# stm32.net
KiCad netlist of a schematic drawn in EasyEDA Pro
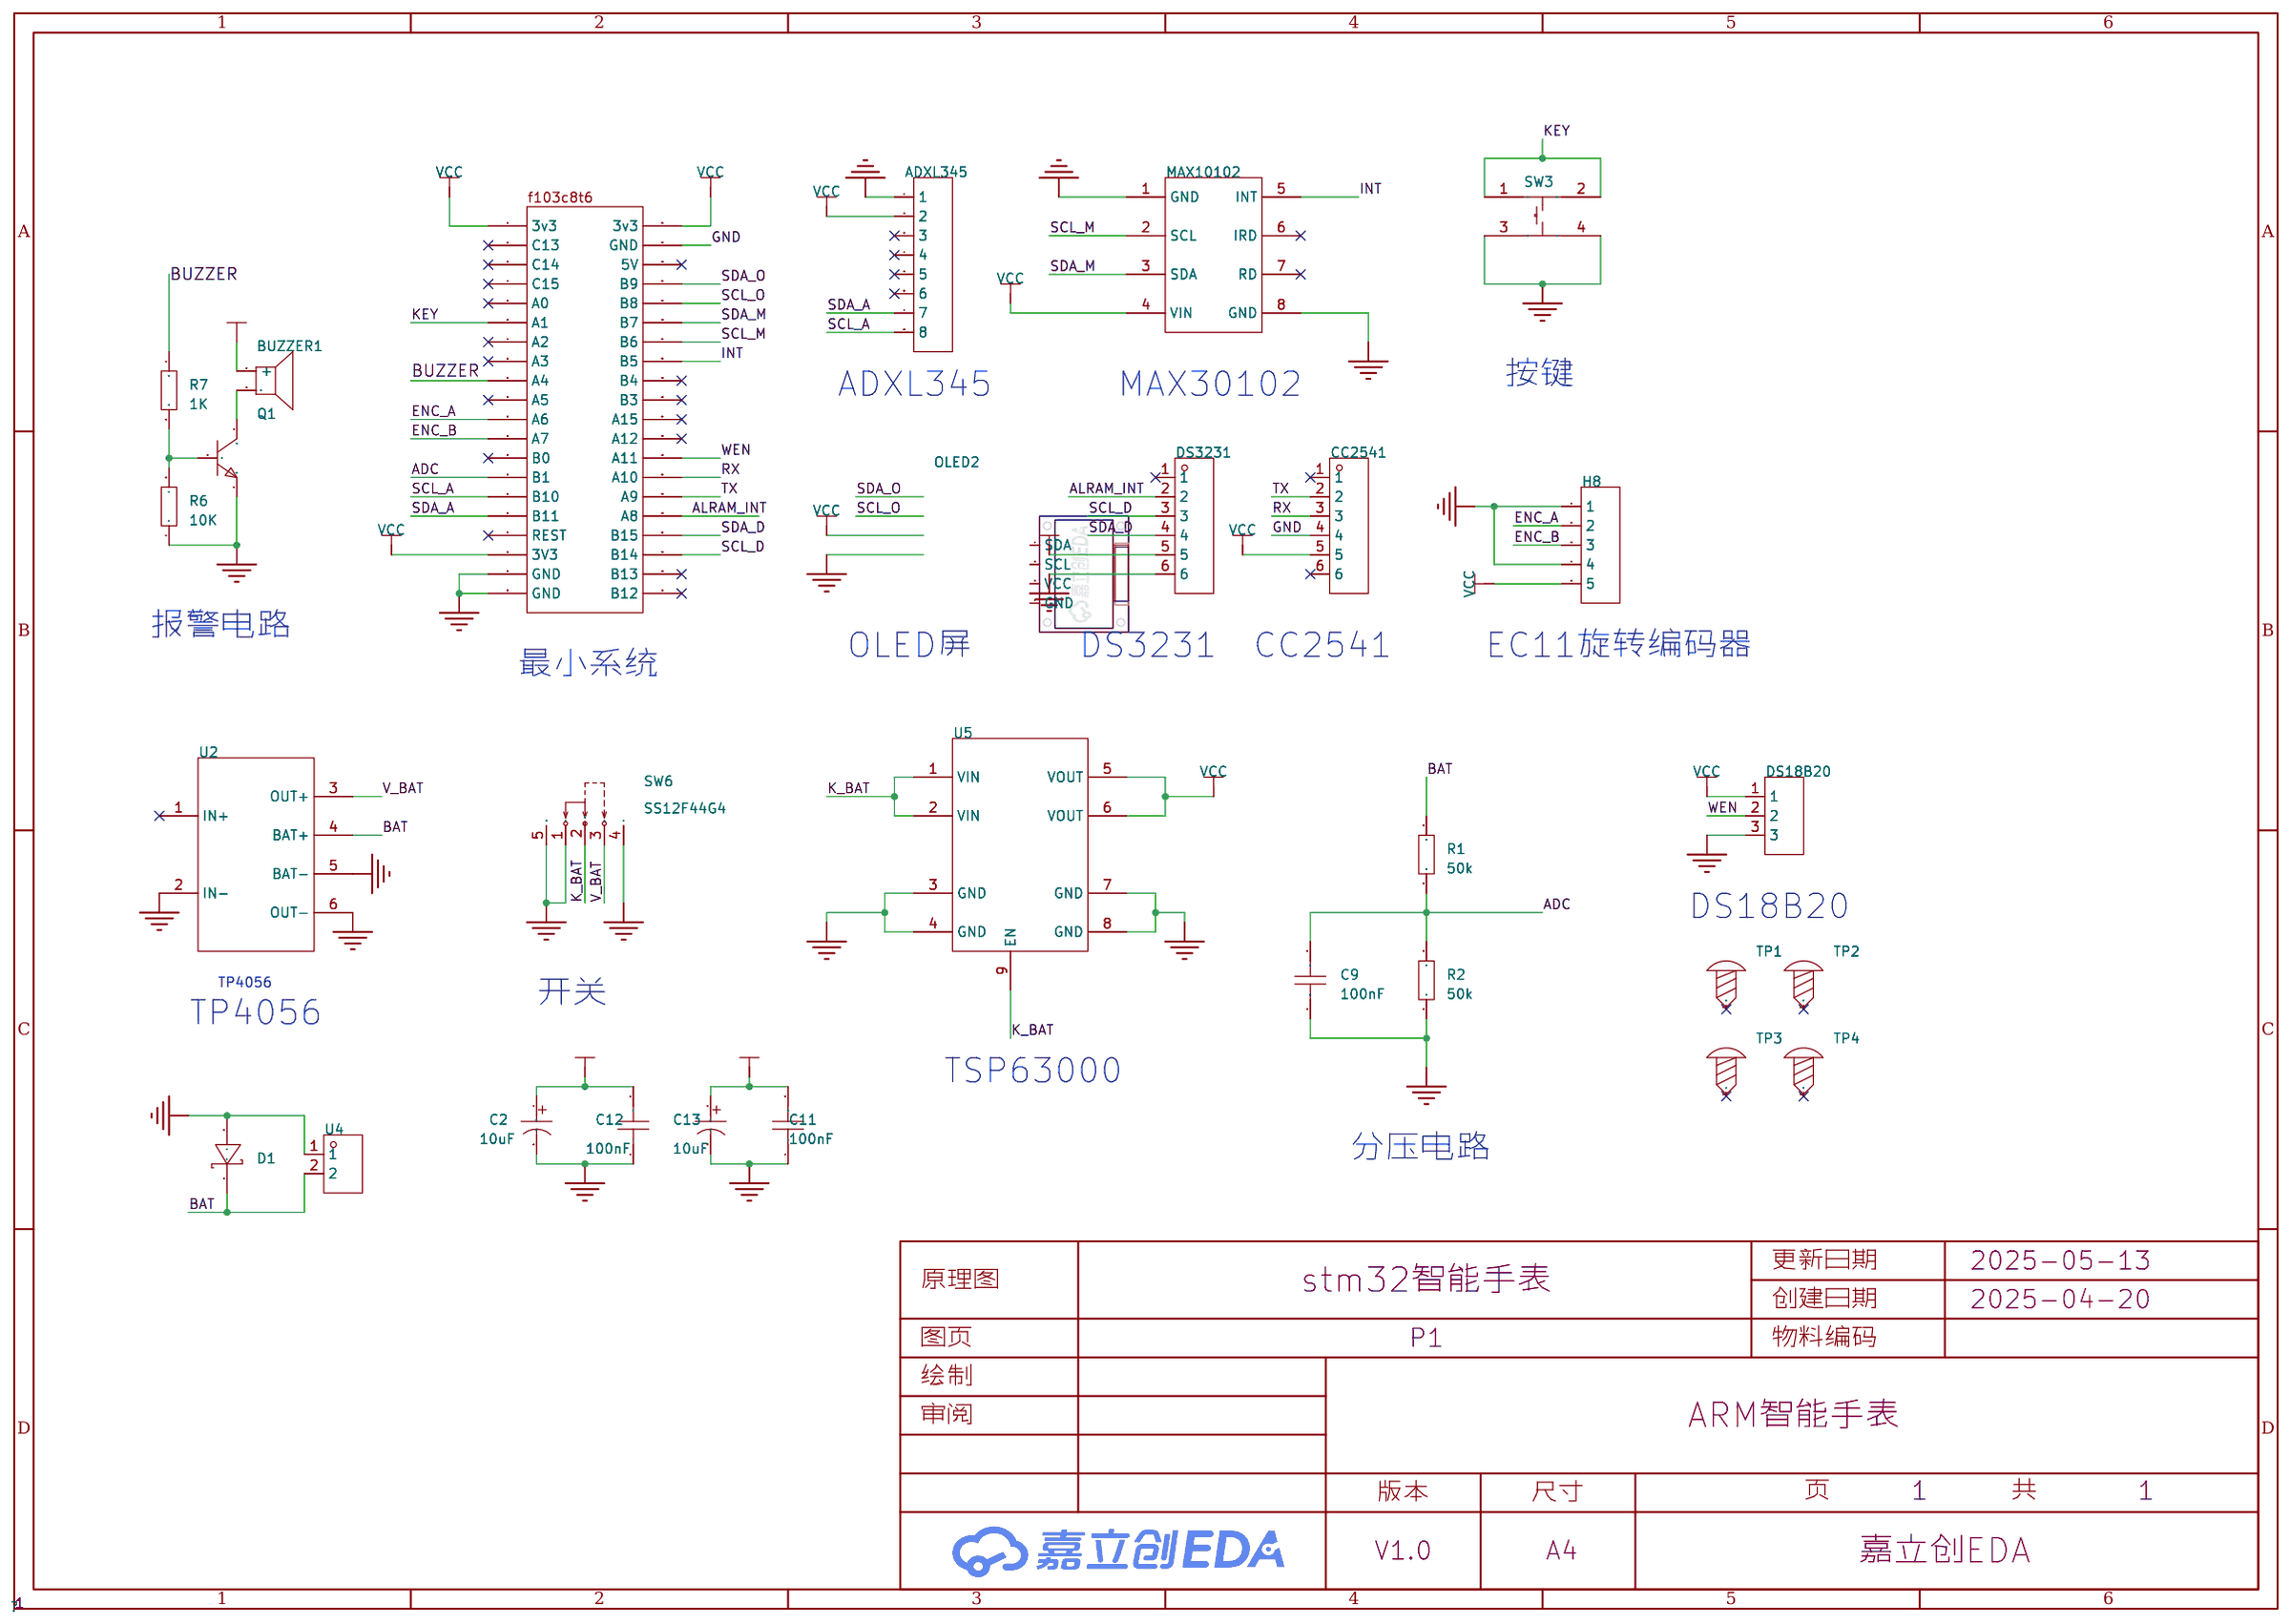
[diagram p0: schematic sheet]

(export (version "E")
  (design (tool "Eeschema 10.0.6"))
  (components
    (comp (ref "ADXL1")
      (value "ADXL345")
      (footprint "easyedapro:HDR-TH_8P-P2.54-V-F-1")
      (libsource (lib "easyedapro") (part "Header-Female-2.54_1x8"))
    )
    (comp (ref "BUZZER1")
      (value "2.3kHz")
      (footprint "easyedapro:BUZ-TH_BD12.0-P7.60-D0.6-FD")
      (description "驱动方式:有源(内含驱动线路);构造类型:电磁式;频率:2.3kHz;声压(SPL):85dB;")
      (fields (field (name "Manufacturer Part") "TMB12A03") (field (name "Manufacturer") "华能"))
      (libsource (lib "easyedapro") (part "TMB12A03"))
    )
    (comp (ref "C2")
      (value "10uF")
      (footprint "easyedapro:CAP-SMD_BD4.0-L4.3-W4.3-FD")
      (description "容值:10uF;精度:±20%;额定电压:35V;纹波电流:15mA@120Hz;等效串联电阻(ESR):-;")
      (fields (field (name "Manufacturer Part") "RVT1V100M0405") (field (name "Manufacturer") "ROQANG(容强)"))
      (libsource (lib "easyedapro") (part "RVT1V100M0405-C72485"))
    )
    (comp (ref "C9")
      (value "100nF")
      (footprint "easyedapro:C0603")
      (libsource (lib "easyedapro") (part "CapAcitance"))
    )
    (comp (ref "C11")
      (value "100nF")
      (footprint "easyedapro:C0603")
      (description "容值:100nF;精度:±10%;额定电压:50V;材质(温度系数):X7R;")
      (fields
        (field (name "Manufacturer Part") "CC0603KRX7R9BB104")
        (field (name "Manufacturer") "YAGEO(国巨)")
      )
      (libsource (lib "easyedapro") (part "CC0603KRX7R9BB104"))
    )
    (comp (ref "C12")
      (value "100nF")
      (footprint "easyedapro:C0603")
      (description "容值:100nF;精度:±10%;额定电压:50V;材质(温度系数):X7R;")
      (fields
        (field (name "Manufacturer Part") "CC0603KRX7R9BB104")
        (field (name "Manufacturer") "YAGEO(国巨)")
      )
      (libsource (lib "easyedapro") (part "CC0603KRX7R9BB104"))
    )
    (comp (ref "C13")
      (value "10uF")
      (footprint "easyedapro:CAP-SMD_BD4.0-L4.3-W4.3-FD")
      (description "容值:10uF;精度:±20%;额定电压:35V;纹波电流:15mA@120Hz;等效串联电阻(ESR):-;")
      (fields (field (name "Manufacturer Part") "RVT1V100M0405") (field (name "Manufacturer") "ROQANG(容强)"))
      (libsource (lib "easyedapro") (part "RVT1V100M0405-C72485"))
    )
    (comp (ref "CC2541")
      (value "~")
      (footprint "easyedapro:HDR-TH_6P-P2.54-V-F")
      (libsource (lib "easyedapro") (part "Header-Female-2.54_1x6"))
    )
    (comp (ref "D1")
      (value "1N5819WS")
      (footprint "easyedapro:SOD-323_L1.8-W1.3-LS2.5-RD")
      (description "正向压降(Vf):600mV@1A;直流反向耐压(Vr):40V;整流电流:1A;")
      (fields (field (name "Manufacturer") "Hottech(合科泰)"))
      (libsource (lib "easyedapro") (part "1N5819WS"))
    )
    (comp (ref "DS1")
      (value "DS3231")
      (footprint "easyedapro:HDR-TH_6P-P2.54-V-F")
      (libsource (lib "easyedapro") (part "Header-Female-2.54_1x6"))
    )
    (comp (ref "H8")
      (value "~")
      (footprint "easyedapro:HDR-TH_5P-P2.54-V-F")
      (libsource (lib "easyedapro") (part "Header-Female-2.54_1x5"))
    )
    (comp (ref "H9")
      (value "DS18B20")
      (footprint "easyedapro:HDR-TH_3P-P2.54-V-F")
      (libsource (lib "easyedapro") (part "PM254V-11-03-H85"))
    )
    (comp (ref "MAX10102")
      (value "~")
      (footprint "easyedapro:MAX30102")
      (libsource (lib "easyedapro") (part "MAX30102"))
    )
    (comp (ref "OLED2")
      (value "~")
      (footprint "easyedapro:0.96OLED_4P")
      (libsource (lib "easyedapro") (part "0.96OLED模块_4P"))
    )
    (comp (ref "Q1")
      (value "~")
      (footprint "easyedapro:S8050_SOT-23")
      (libsource (lib "easyedapro") (part "NPN"))
    )
    (comp (ref "R1") (value "50k") (footprint "easyedapro:R0603") (libsource (lib "easyedapro") (part "电阻")))
    (comp (ref "R2") (value "50k") (footprint "easyedapro:R0603") (libsource (lib "easyedapro") (part "电阻")))
    (comp (ref "R6") (value "10K") (libsource (lib "easyedapro") (part "电阻")))
    (comp (ref "R7") (value "1K") (libsource (lib "easyedapro") (part "电阻")))
    (comp (ref "SCREW1")
      (value "TP1")
      (footprint "easyedapro:M3螺丝")
      (libsource (lib "easyedapro") (part "螺丝孔"))
    )
    (comp (ref "SCREW2")
      (value "TP2")
      (footprint "easyedapro:M3螺丝")
      (libsource (lib "easyedapro") (part "螺丝孔"))
    )
    (comp (ref "SCREW3")
      (value "TP3")
      (footprint "easyedapro:M3螺丝")
      (libsource (lib "easyedapro") (part "螺丝孔"))
    )
    (comp (ref "SCREW4")
      (value "TP4")
      (footprint "easyedapro:M3螺丝")
      (libsource (lib "easyedapro") (part "螺丝孔"))
    )
    (comp (ref "SW3")
      (value "TS-1002-07026")
      (footprint "easyedapro:SW-TH_4P-L6.0-W6.0-P4.50-LS6.5")
      (description "电路结构:单刀单掷;按钮形状:圆形按钮;安装方式:直插;开关长度:6mm;开关宽度:6mm;开关高度:7mm;触点电流:50mA;额定电压(DC):12V;带灯:-;机械寿命:-;")
      (fields (field (name "Manufacturer") "XUNPU(讯普)"))
      (libsource (lib "easyedapro") (part "TS-1002-07026"))
    )
    (comp (ref "SW6")
      (value "SS12F44G4")
      (footprint "easyedapro:SW-TH_SHOU-HAN_SS12F44G4")
      (description "电路结构:单刀双掷;安装方式:直插;开关颜色:-;额定电流(DC):300mA;额定电压(DC):50V;额定电流(AC):-;额定电压(AC):-;机械寿命:5千次;")
      (fields (field (name "Manufacturer") "SHOU HAN(首韩)"))
      (libsource (lib "easyedapro") (part "SS12F44G4"))
    )
    (comp (ref "U1")
      (value "~")
      (footprint "easyedapro:stm32f103c8t6最小系统板")
      (libsource (lib "easyedapro") (part "stm32f103c8t6最小系统板"))
    )
    (comp (ref "U2")
      (value "~")
      (footprint "easyedapro:TP4056")
      (libsource (lib "easyedapro") (part "TP4056模块"))
    )
    (comp (ref "U4")
      (value "XY-XHB2.54-2A21")
      (footprint "easyedapro:HDR-TH_2P-P2.50-H-F-W7.3-N")
      (description "插针结构:1x2P;间距:2.54mm;安装方式:弯插;总PIN数:2P;排数:1;每排PIN数:2;行距:2.54mm;额定电流:2A;工作温度范围:-25°C~+85°C;")
      (fields (field (name "Manufacturer") "XYECONN(辛译)"))
      (libsource (lib "easyedapro") (part "XY-XHB2.54-2A21"))
    )
    (comp (ref "U5")
      (value "~")
      (footprint "easyedapro:TPS63000")
      (libsource (lib "easyedapro") (part "TPS63000"))
    )
  )
  (nets
    (net (code "1") (name "/ADC") (class "Default")
      (node (ref "C9") (pin "2") (pinfunction "2_2") (pintype "input"))
      (node (ref "R1") (pin "1") (pinfunction "1_1") (pintype "input"))
      (node (ref "R2") (pin "2") (pinfunction "2_2") (pintype "input"))
      (node (ref "U1") (pin "14") (pinfunction "B1_14") (pintype "input"))
    )
    (net (code "2") (name "/ALRAM_INT") (class "Default")
      (node (ref "DS1") (pin "2") (pinfunction "2_2") (pintype "unspecified"))
      (node (ref "U1") (pin "36") (pinfunction "A8_36") (pintype "input"))
    )
    (net (code "3") (name "/BAT") (class "Default")
      (node (ref "D1") (pin "1") (pinfunction "K_1") (pintype "unspecified"))
      (node (ref "R1") (pin "2") (pinfunction "2_2") (pintype "input"))
      (node (ref "U2") (pin "4") (pinfunction "BAT+_4") (pintype "input"))
      (node (ref "U4") (pin "2") (pinfunction "2_2") (pintype "unspecified"))
    )
    (net (code "4") (name "/BUZZER") (class "Default")
      (node (ref "R7") (pin "1") (pinfunction "1_1") (pintype "input"))
      (node (ref "U1") (pin "9") (pinfunction "A4_9") (pintype "input"))
    )
    (net (code "5") (name "/ENC_A") (class "Default")
      (node (ref "H8") (pin "2") (pinfunction "2_2") (pintype "input"))
      (node (ref "U1") (pin "11") (pinfunction "A6_11") (pintype "input"))
    )
    (net (code "6") (name "/ENC_B") (class "Default")
      (node (ref "H8") (pin "3") (pinfunction "3_3") (pintype "input"))
      (node (ref "U1") (pin "12") (pinfunction "A7_12") (pintype "input"))
    )
    (net (code "7") (name "/INT") (class "Default")
      (node (ref "MAX10102") (pin "5") (pinfunction "INT_5") (pintype "input"))
      (node (ref "U1") (pin "28") (pinfunction "B5_28") (pintype "input"))
    )
    (net (code "8") (name "/KEY") (class "Default")
      (node (ref "SW3") (pin "1") (pinfunction "1_1") (pintype "unspecified"))
      (node (ref "SW3") (pin "2") (pinfunction "2_2") (pintype "unspecified"))
      (node (ref "U1") (pin "6") (pinfunction "A1_6") (pintype "input"))
    )
    (net (code "9") (name "/RX") (class "Default")
      (node (ref "CC2541") (pin "3") (pinfunction "3_3") (pintype "unspecified"))
      (node (ref "U1") (pin "34") (pinfunction "A10_34") (pintype "input"))
    )
    (net (code "10") (name "/SCL_A") (class "Default")
      (node (ref "ADXL1") (pin "8") (pinfunction "8_8") (pintype "input"))
      (node (ref "U1") (pin "15") (pinfunction "B10_15") (pintype "input"))
    )
    (net (code "11") (name "/SCL_D") (class "Default")
      (node (ref "DS1") (pin "3") (pinfunction "3_3") (pintype "unspecified"))
      (node (ref "U1") (pin "38") (pinfunction "B14_38") (pintype "input"))
    )
    (net (code "12") (name "/SCL_M") (class "Default")
      (node (ref "MAX10102") (pin "2") (pinfunction "SCL_2") (pintype "input"))
      (node (ref "U1") (pin "27") (pinfunction "B6_27") (pintype "input"))
    )
    (net (code "13") (name "/SCL_O") (class "Default")
      (node (ref "U1") (pin "25") (pinfunction "B8_25") (pintype "input"))
    )
    (net (code "14") (name "/SDA_A") (class "Default")
      (node (ref "ADXL1") (pin "7") (pinfunction "7_7") (pintype "input"))
      (node (ref "U1") (pin "16") (pinfunction "B11_16") (pintype "input"))
    )
    (net (code "15") (name "/SDA_D") (class "Default")
      (node (ref "DS1") (pin "4") (pinfunction "4_4") (pintype "unspecified"))
      (node (ref "U1") (pin "37") (pinfunction "B15_37") (pintype "input"))
    )
    (net (code "16") (name "/SDA_M") (class "Default")
      (node (ref "MAX10102") (pin "3") (pinfunction "SDA_3") (pintype "input"))
      (node (ref "U1") (pin "26") (pinfunction "B7_26") (pintype "input"))
    )
    (net (code "17") (name "/SDA_O") (class "Default")
      (node (ref "U1") (pin "24") (pinfunction "B9_24") (pintype "input"))
    )
    (net (code "18") (name "/TX") (class "Default")
      (node (ref "CC2541") (pin "2") (pinfunction "2_2") (pintype "unspecified"))
      (node (ref "U1") (pin "35") (pinfunction "A9_35") (pintype "input"))
    )
    (net (code "19") (name "/V_BAT") (class "Default")
      (node (ref "SW6") (pin "3") (pinfunction "3_3") (pintype "unspecified"))
      (node (ref "U2") (pin "3") (pinfunction "OUT+_3") (pintype "input"))
    )
    (net (code "20") (name "/WEN") (class "Default")
      (node (ref "H9") (pin "2") (pinfunction "2_2") (pintype "unspecified"))
      (node (ref "U1") (pin "33") (pinfunction "A11_33") (pintype "input"))
    )
    (net (code "21") (name "GND") (class "Default")
      (node (ref "ADXL1") (pin "1") (pinfunction "1_1") (pintype "input"))
      (node (ref "C11") (pin "1") (pinfunction "1_1") (pintype "unspecified"))
      (node (ref "C12") (pin "1") (pinfunction "1_1") (pintype "unspecified"))
      (node (ref "C13") (pin "2") (pinfunction "2_2") (pintype "input"))
      (node (ref "C2") (pin "2") (pinfunction "2_2") (pintype "input"))
      (node (ref "C9") (pin "1") (pinfunction "1_1") (pintype "input"))
      (node (ref "CC2541") (pin "4") (pinfunction "4_4") (pintype "unspecified"))
      (node (ref "D1") (pin "2") (pinfunction "A_2") (pintype "unspecified"))
      (node (ref "DS1") (pin "6") (pinfunction "6_6") (pintype "unspecified"))
      (node (ref "H8") (pin "1") (pinfunction "1_1") (pintype "input"))
      (node (ref "H8") (pin "4") (pinfunction "4_4") (pintype "input"))
      (node (ref "H9") (pin "3") (pinfunction "3_3") (pintype "unspecified"))
      (node (ref "MAX10102") (pin "1") (pinfunction "GND_1") (pintype "input"))
      (node (ref "MAX10102") (pin "8") (pinfunction "GND_8") (pintype "input"))
      (node (ref "Q1") (pin "2") (pinfunction "2_2") (pintype "unspecified"))
      (node (ref "R2") (pin "1") (pinfunction "1_1") (pintype "input"))
      (node (ref "R6") (pin "1") (pinfunction "1_1") (pintype "input"))
      (node (ref "SW3") (pin "3") (pinfunction "3_3") (pintype "unspecified"))
      (node (ref "SW3") (pin "4") (pinfunction "4_4") (pintype "unspecified"))
      (node (ref "SW6") (pin "1") (pinfunction "1_1") (pintype "unspecified"))
      (node (ref "SW6") (pin "4") (pinfunction "4_4") (pintype "unspecified"))
      (node (ref "SW6") (pin "5") (pinfunction "5_5") (pintype "unspecified"))
      (node (ref "U1") (pin "19") (pinfunction "GND_19") (pintype "input"))
      (node (ref "U1") (pin "20") (pinfunction "GND_20") (pintype "input"))
      (node (ref "U1") (pin "22") (pinfunction "GND_22") (pintype "input"))
      (node (ref "U2") (pin "2") (pinfunction "IN-_2") (pintype "input"))
      (node (ref "U2") (pin "5") (pinfunction "BAT-_5") (pintype "input"))
      (node (ref "U2") (pin "6") (pinfunction "OUT-_6") (pintype "input"))
      (node (ref "U4") (pin "1") (pinfunction "1_1") (pintype "unspecified"))
      (node (ref "U5") (pin "3") (pinfunction "GND_3") (pintype "input"))
      (node (ref "U5") (pin "4") (pinfunction "GND_4") (pintype "input"))
      (node (ref "U5") (pin "7") (pinfunction "GND_7") (pintype "input"))
      (node (ref "U5") (pin "8") (pinfunction "GND_8") (pintype "input"))
    )
    (net (code "22") (name "K_BAT") (class "Default")
      (node (ref "C12") (pin "2") (pinfunction "2_2") (pintype "unspecified"))
      (node (ref "C2") (pin "1") (pinfunction "1_1") (pintype "input"))
      (node (ref "SW6") (pin "2") (pinfunction "2_2") (pintype "unspecified"))
      (node (ref "U5") (pin "1") (pinfunction "VIN_1") (pintype "input"))
      (node (ref "U5") (pin "2") (pinfunction "VIN_2") (pintype "input"))
      (node (ref "U5") (pin "9") (pinfunction "EN_9") (pintype "input"))
    )
    (net (code "23") (name "Net-(BUZZER1-Pad2)") (class "Default")
      (node (ref "BUZZER1") (pin "2") (pinfunction "2_2") (pintype "unspecified"))
      (node (ref "Q1") (pin "3") (pinfunction "3_3") (pintype "unspecified"))
    )
    (net (code "24") (name "Net-(Q1-Pad1)") (class "Default")
      (node (ref "Q1") (pin "1") (pinfunction "1_1") (pintype "unspecified"))
      (node (ref "R6") (pin "2") (pinfunction "2_2") (pintype "input"))
      (node (ref "R7") (pin "2") (pinfunction "2_2") (pintype "input"))
    )
    (net (code "25") (name "VCC") (class "Default")
      (node (ref "ADXL1") (pin "2") (pinfunction "2_2") (pintype "input"))
      (node (ref "BUZZER1") (pin "1") (pinfunction "+_1") (pintype "unspecified"))
      (node (ref "C11") (pin "2") (pinfunction "2_2") (pintype "unspecified"))
      (node (ref "C13") (pin "1") (pinfunction "1_1") (pintype "input"))
      (node (ref "CC2541") (pin "5") (pinfunction "5_5") (pintype "unspecified"))
      (node (ref "DS1") (pin "5") (pinfunction "5_5") (pintype "unspecified"))
      (node (ref "H8") (pin "5") (pinfunction "5_5") (pintype "input"))
      (node (ref "H9") (pin "1") (pinfunction "1_1") (pintype "unspecified"))
      (node (ref "MAX10102") (pin "4") (pinfunction "VIN_4") (pintype "input"))
      (node (ref "U1") (pin "1") (pinfunction "3v3_1") (pintype "input"))
      (node (ref "U1") (pin "18") (pinfunction "3V3_18") (pintype "input"))
      (node (ref "U1") (pin "21") (pinfunction "3v3_21") (pintype "input"))
      (node (ref "U5") (pin "5") (pinfunction "VOUT_5") (pintype "input"))
      (node (ref "U5") (pin "6") (pinfunction "VOUT_6") (pintype "input"))
    )
    (net (code "26") (name "unconnected-(ADXL1-Pad3)") (class "Default")
      (node (ref "ADXL1") (pin "3") (pinfunction "3_3") (pintype "input+no_connect"))
    )
    (net (code "27") (name "unconnected-(ADXL1-Pad4)") (class "Default")
      (node (ref "ADXL1") (pin "4") (pinfunction "4_4") (pintype "input+no_connect"))
    )
    (net (code "28") (name "unconnected-(ADXL1-Pad5)") (class "Default")
      (node (ref "ADXL1") (pin "5") (pinfunction "5_5") (pintype "input+no_connect"))
    )
    (net (code "29") (name "unconnected-(ADXL1-Pad6)") (class "Default")
      (node (ref "ADXL1") (pin "6") (pinfunction "6_6") (pintype "input+no_connect"))
    )
    (net (code "30") (name "unconnected-(CC2541-Pad1)") (class "Default")
      (node (ref "CC2541") (pin "1") (pinfunction "1_1") (pintype "unspecified+no_connect"))
    )
    (net (code "31") (name "unconnected-(CC2541-Pad6)") (class "Default")
      (node (ref "CC2541") (pin "6") (pinfunction "6_6") (pintype "unspecified+no_connect"))
    )
    (net (code "32") (name "unconnected-(DS1-Pad1)") (class "Default")
      (node (ref "DS1") (pin "1") (pinfunction "1_1") (pintype "unspecified+no_connect"))
    )
    (net (code "33") (name "unconnected-(MAX10102-IRD-Pad6)") (class "Default")
      (node (ref "MAX10102") (pin "6") (pinfunction "IRD_6") (pintype "input+no_connect"))
    )
    (net (code "34") (name "unconnected-(MAX10102-RD-Pad7)") (class "Default")
      (node (ref "MAX10102") (pin "7") (pinfunction "RD_7") (pintype "input+no_connect"))
    )
    (net (code "35") (name "unconnected-(OLED2-GND-Pad1)") (class "Default")
      (node (ref "OLED2") (pin "1") (pinfunction "GND_1") (pintype "input"))
    )
    (net (code "36") (name "unconnected-(OLED2-SCL-Pad3)") (class "Default")
      (node (ref "OLED2") (pin "3") (pinfunction "SCL_3") (pintype "input"))
    )
    (net (code "37") (name "unconnected-(OLED2-SDA-Pad4)") (class "Default")
      (node (ref "OLED2") (pin "4") (pinfunction "SDA_4") (pintype "input"))
    )
    (net (code "38") (name "unconnected-(OLED2-VCC-Pad2)") (class "Default")
      (node (ref "OLED2") (pin "2") (pinfunction "VCC_2") (pintype "input"))
    )
    (net (code "39") (name "unconnected-(SCREW1-Pad1)") (class "Default")
      (node (ref "SCREW1") (pin "1") (pinfunction "1_1") (pintype "input+no_connect"))
    )
    (net (code "40") (name "unconnected-(SCREW2-Pad1)") (class "Default")
      (node (ref "SCREW2") (pin "1") (pinfunction "1_1") (pintype "input+no_connect"))
    )
    (net (code "41") (name "unconnected-(SCREW3-Pad1)") (class "Default")
      (node (ref "SCREW3") (pin "1") (pinfunction "1_1") (pintype "input+no_connect"))
    )
    (net (code "42") (name "unconnected-(SCREW4-Pad1)") (class "Default")
      (node (ref "SCREW4") (pin "1") (pinfunction "1_1") (pintype "input+no_connect"))
    )
    (net (code "43") (name "unconnected-(U1-5V-Pad23)") (class "Default")
      (node (ref "U1") (pin "23") (pinfunction "5V_23") (pintype "input+no_connect"))
    )
    (net (code "44") (name "unconnected-(U1-A0-Pad5)") (class "Default")
      (node (ref "U1") (pin "5") (pinfunction "A0_5") (pintype "input+no_connect"))
    )
    (net (code "45") (name "unconnected-(U1-A2-Pad7)") (class "Default")
      (node (ref "U1") (pin "7") (pinfunction "A2_7") (pintype "input+no_connect"))
    )
    (net (code "46") (name "unconnected-(U1-A3-Pad8)") (class "Default")
      (node (ref "U1") (pin "8") (pinfunction "A3_8") (pintype "input+no_connect"))
    )
    (net (code "47") (name "unconnected-(U1-A5-Pad10)") (class "Default")
      (node (ref "U1") (pin "10") (pinfunction "A5_10") (pintype "input+no_connect"))
    )
    (net (code "48") (name "unconnected-(U1-A12-Pad32)") (class "Default")
      (node (ref "U1") (pin "32") (pinfunction "A12_32") (pintype "input+no_connect"))
    )
    (net (code "49") (name "unconnected-(U1-A15-Pad31)") (class "Default")
      (node (ref "U1") (pin "31") (pinfunction "A15_31") (pintype "input+no_connect"))
    )
    (net (code "50") (name "unconnected-(U1-B0-Pad13)") (class "Default")
      (node (ref "U1") (pin "13") (pinfunction "B0_13") (pintype "input+no_connect"))
    )
    (net (code "51") (name "unconnected-(U1-B3-Pad30)") (class "Default")
      (node (ref "U1") (pin "30") (pinfunction "B3_30") (pintype "input+no_connect"))
    )
    (net (code "52") (name "unconnected-(U1-B4-Pad29)") (class "Default")
      (node (ref "U1") (pin "29") (pinfunction "B4_29") (pintype "input+no_connect"))
    )
    (net (code "53") (name "unconnected-(U1-B12-Pad40)") (class "Default")
      (node (ref "U1") (pin "40") (pinfunction "B12_40") (pintype "input+no_connect"))
    )
    (net (code "54") (name "unconnected-(U1-B13-Pad39)") (class "Default")
      (node (ref "U1") (pin "39") (pinfunction "B13_39") (pintype "input+no_connect"))
    )
    (net (code "55") (name "unconnected-(U1-C13-Pad2)") (class "Default")
      (node (ref "U1") (pin "2") (pinfunction "C13_2") (pintype "input+no_connect"))
    )
    (net (code "56") (name "unconnected-(U1-C14-Pad3)") (class "Default")
      (node (ref "U1") (pin "3") (pinfunction "C14_3") (pintype "input+no_connect"))
    )
    (net (code "57") (name "unconnected-(U1-C15-Pad4)") (class "Default")
      (node (ref "U1") (pin "4") (pinfunction "C15_4") (pintype "input+no_connect"))
    )
    (net (code "58") (name "unconnected-(U1-REST-Pad17)") (class "Default")
      (node (ref "U1") (pin "17") (pinfunction "REST_17") (pintype "input+no_connect"))
    )
    (net (code "59") (name "unconnected-(U2-IN+-Pad1)") (class "Default")
      (node (ref "U2") (pin "1") (pinfunction "IN+_1") (pintype "input+no_connect"))
    )
  )
)
